# HealthMonitor.net
KiCad netlist of a schematic drawn in EAGLE
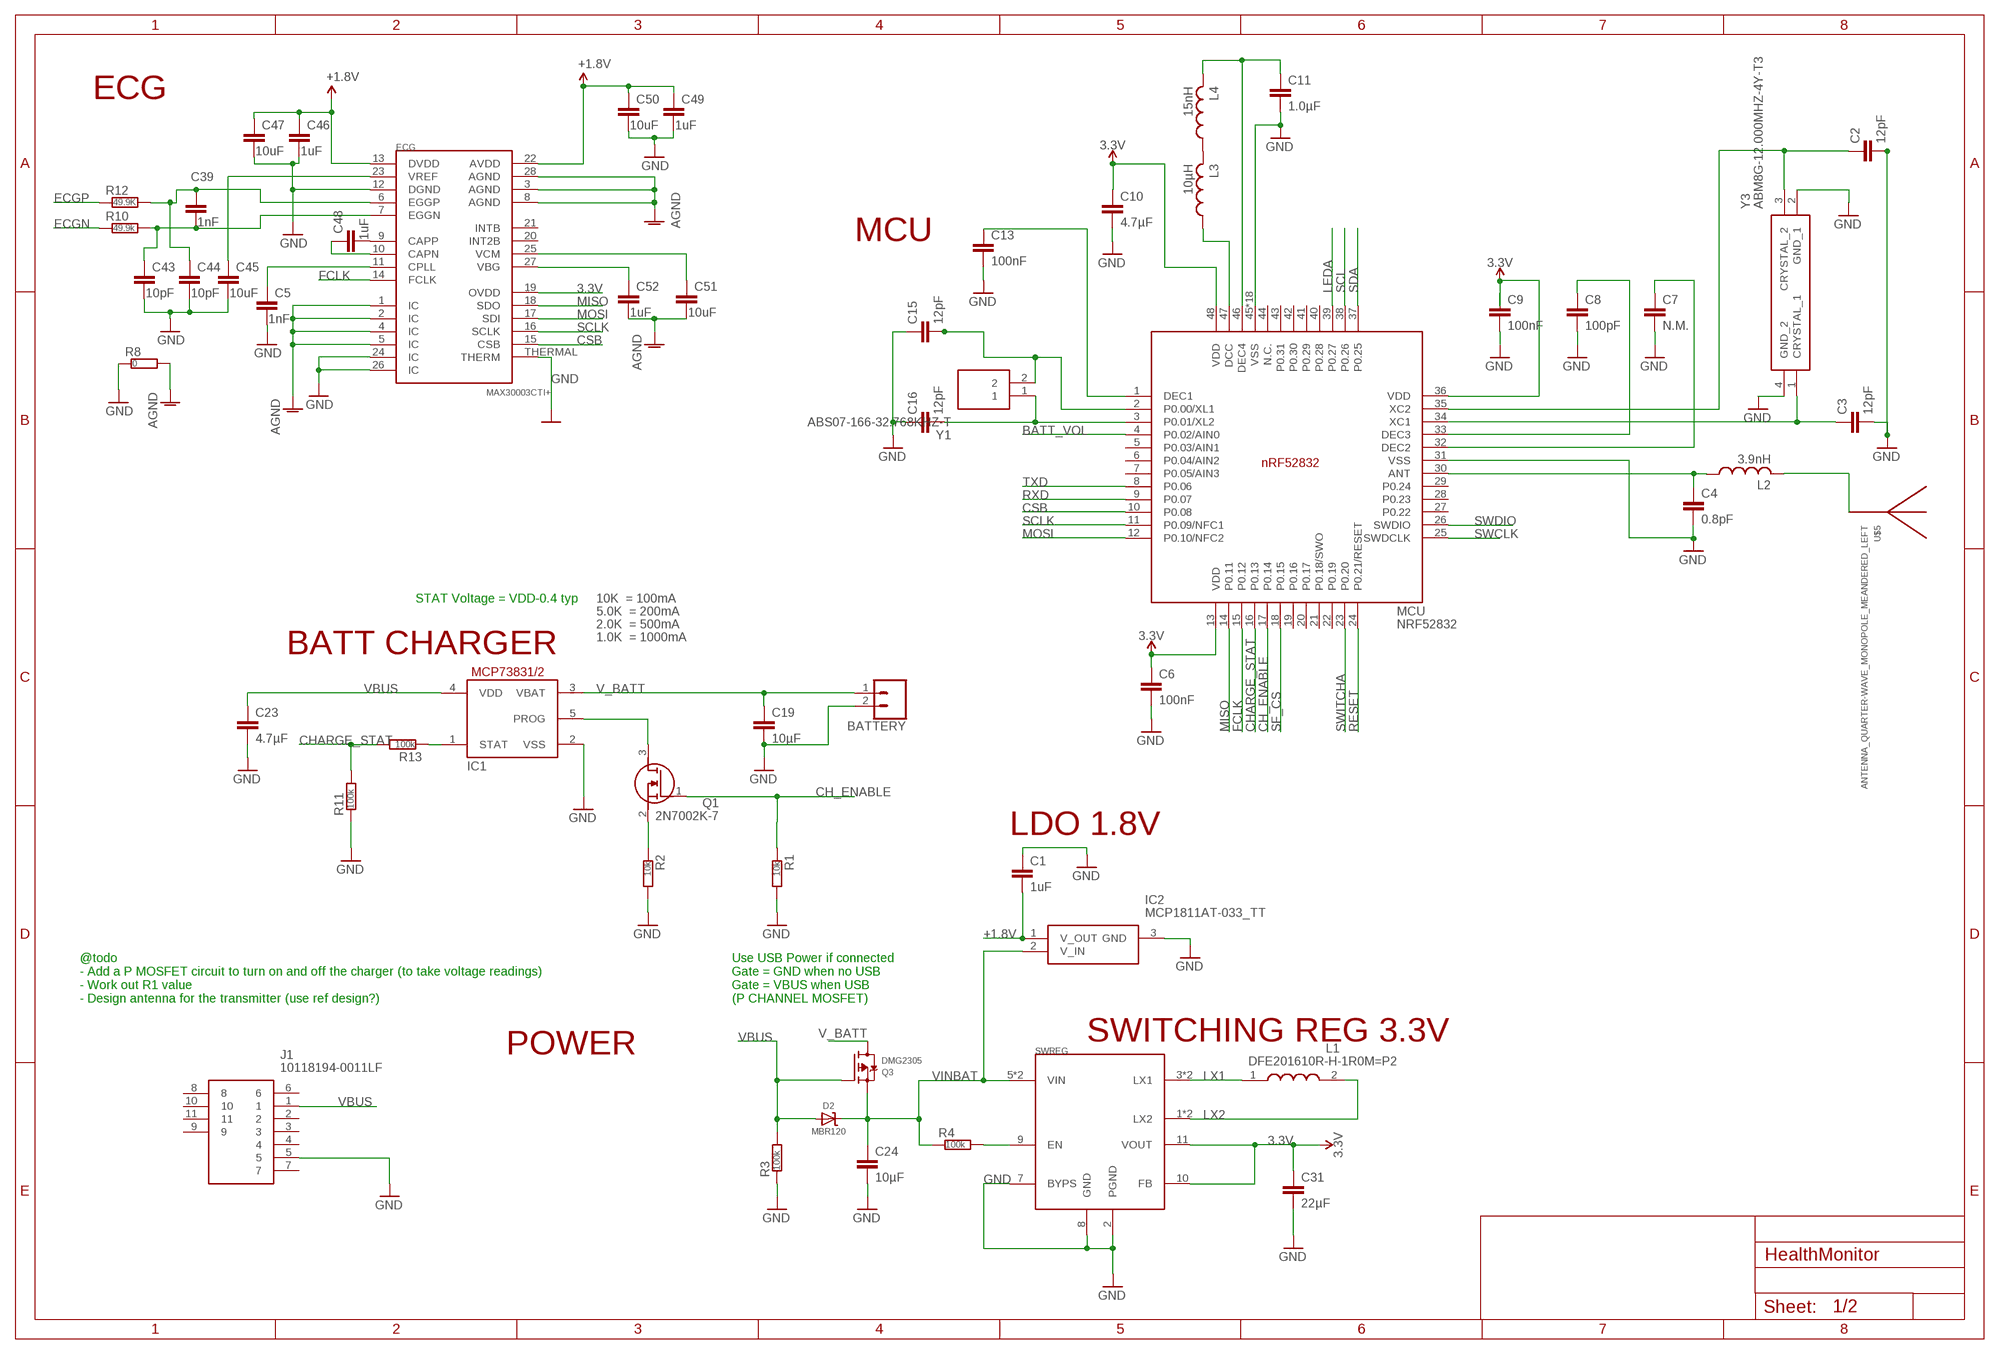
[diagram p0: schematic, sheet 1]
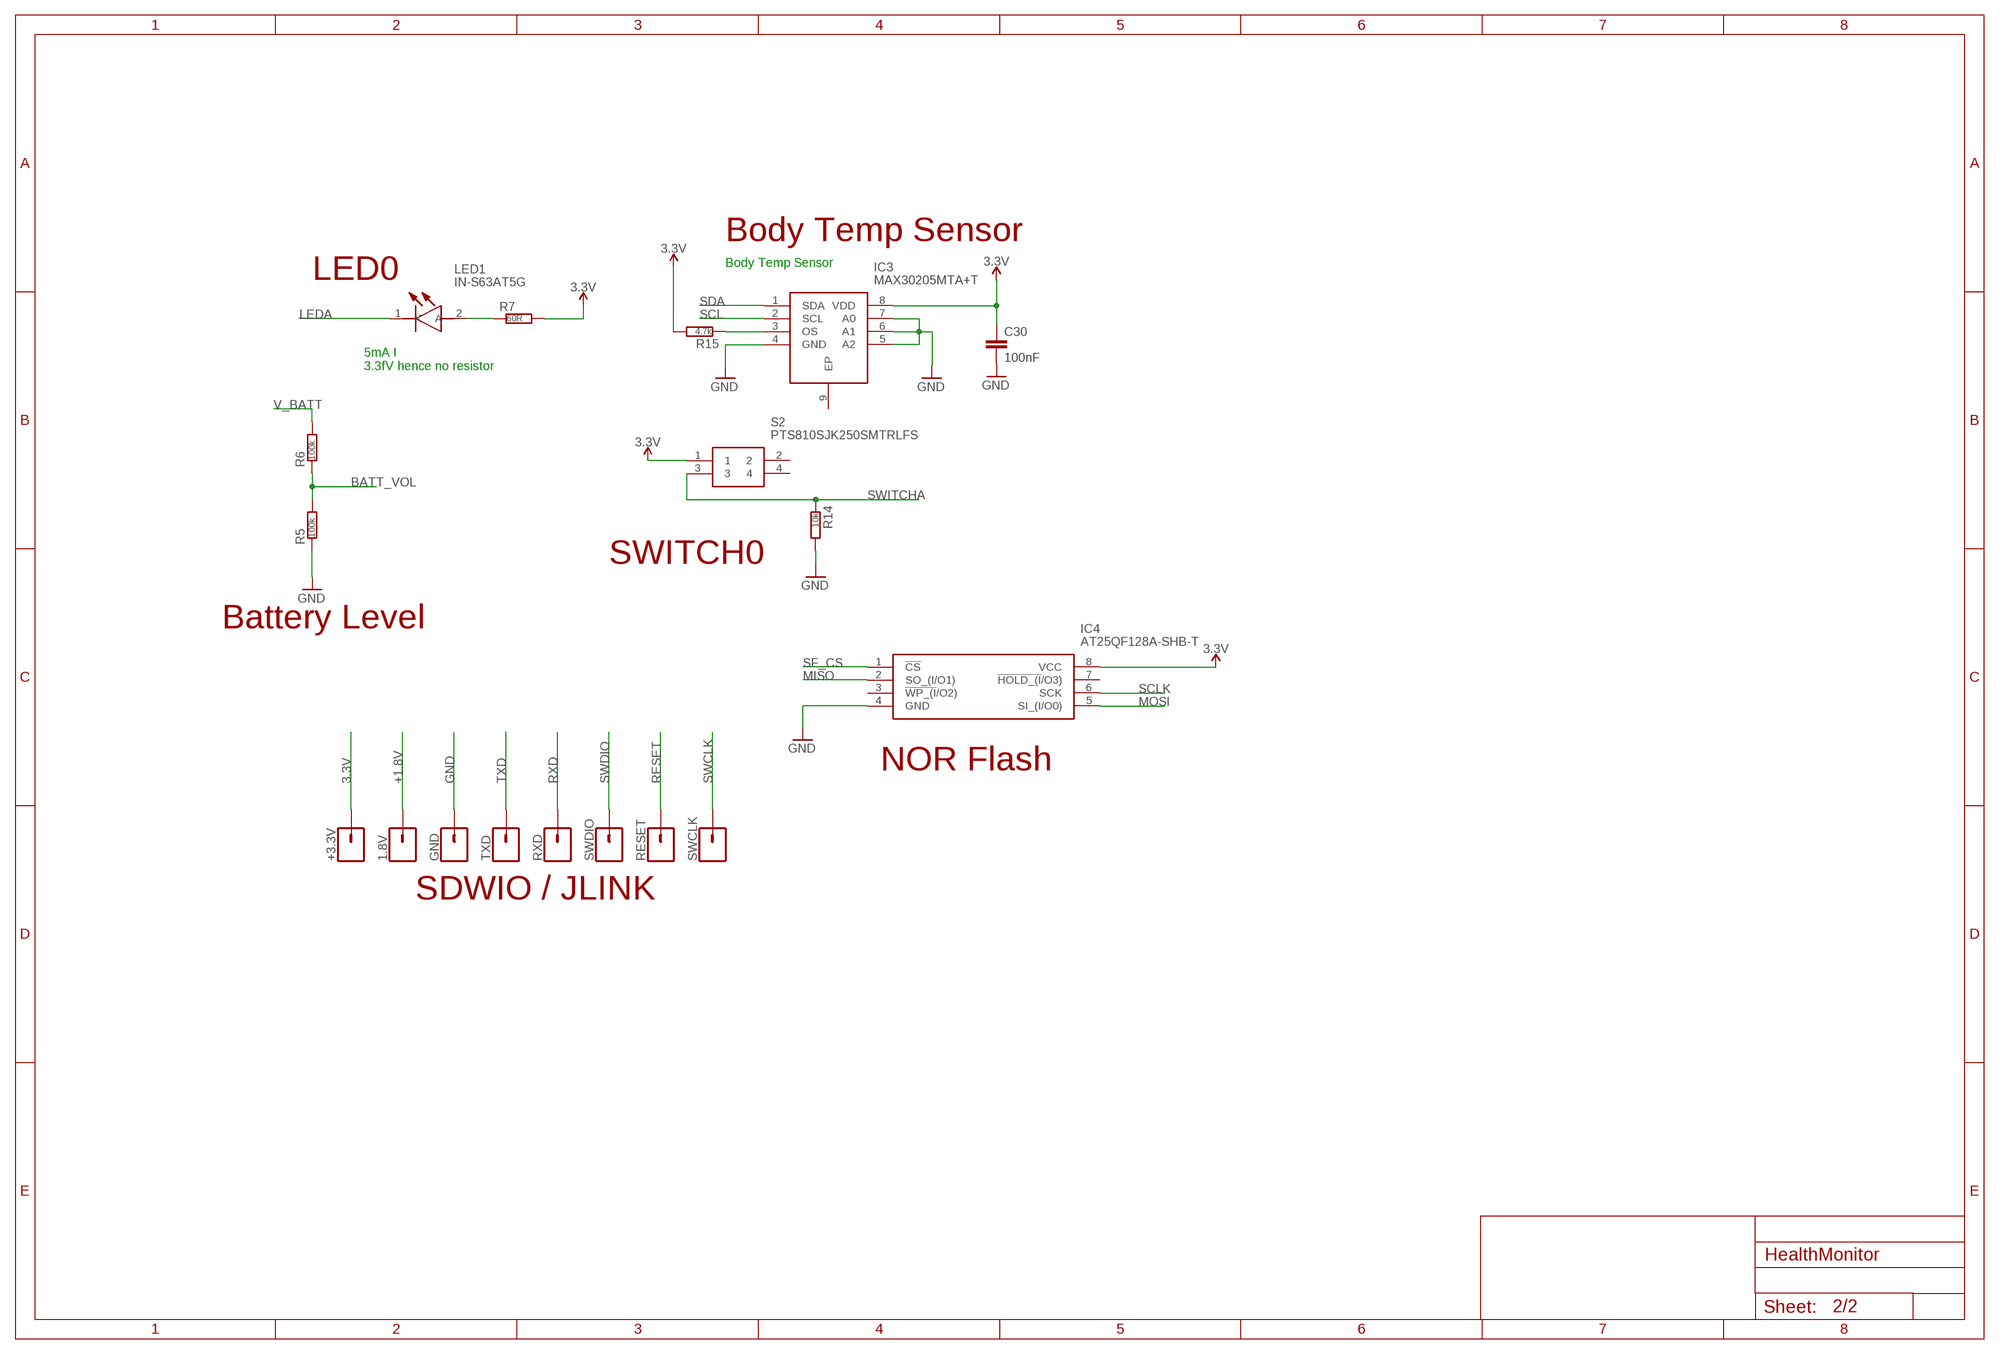
[diagram p1: schematic, sheet 2]

(export (version "E")
  (design (tool "Eeschema 10.0.6"))
  (components
    (comp (ref "BATTERY")
      (value "CONN_02")
      (footprint "eagle-import:1X02")
      (libsource (lib "eagle-import") (part "CONN_02"))
    )
    (comp (ref "C1")
      (value "1uF")
      (footprint "eagle-import:RESC0603_N")
      (libsource (lib "eagle-import") (part "CAPACITOR_0603_N"))
    )
    (comp (ref "C2")
      (value "12pF")
      (footprint "eagle-import:RESC0603_N")
      (libsource (lib "eagle-import") (part "CAPACITOR_0603_N"))
    )
    (comp (ref "C3")
      (value "12pF")
      (footprint "eagle-import:RESC0603_N")
      (libsource (lib "eagle-import") (part "CAPACITOR_0603_N"))
    )
    (comp (ref "C4")
      (value "0.8pF")
      (footprint "eagle-import:RESC0603_N")
      (libsource (lib "eagle-import") (part "CAPACITOR_0603_N"))
    )
    (comp (ref "C5")
      (value "1nF")
      (footprint "eagle-import:RESC0603_N")
      (libsource (lib "eagle-import") (part "CAPACITOR_0603_N"))
    )
    (comp (ref "C6")
      (value "100nF")
      (footprint "eagle-import:RESC0603_N")
      (libsource (lib "eagle-import") (part "CAPACITOR_0603_N"))
    )
    (comp (ref "C7")
      (value "N.M.")
      (footprint "eagle-import:RESC0603_N")
      (libsource (lib "eagle-import") (part "CAPACITOR_0603_N"))
    )
    (comp (ref "C8")
      (value "100pF")
      (footprint "eagle-import:RESC0603_N")
      (libsource (lib "eagle-import") (part "CAPACITOR_0603_N"))
    )
    (comp (ref "C9")
      (value "100nF")
      (footprint "eagle-import:RESC0603_N")
      (libsource (lib "eagle-import") (part "CAPACITOR_0603_N"))
    )
    (comp (ref "C10")
      (value "4.7µF")
      (footprint "eagle-import:RESC0603_N")
      (libsource (lib "eagle-import") (part "CAPACITOR_0603_N"))
    )
    (comp (ref "C11")
      (value "1.0µF")
      (footprint "eagle-import:RESC0603_N")
      (libsource (lib "eagle-import") (part "CAPACITOR_0603_N"))
    )
    (comp (ref "C13")
      (value "100nF")
      (footprint "eagle-import:RESC0603_N")
      (libsource (lib "eagle-import") (part "CAPACITOR_0603_N"))
    )
    (comp (ref "C15")
      (value "12pF")
      (footprint "eagle-import:RESC0603_N")
      (libsource (lib "eagle-import") (part "CAPACITOR_0603_N"))
    )
    (comp (ref "C16")
      (value "12pF")
      (footprint "eagle-import:RESC0603_N")
      (libsource (lib "eagle-import") (part "CAPACITOR_0603_N"))
    )
    (comp (ref "C19")
      (value "10µF")
      (footprint "eagle-import:RESC0603_N")
      (libsource (lib "eagle-import") (part "CAPACITOR_0603_N"))
    )
    (comp (ref "C23")
      (value "4.7µF")
      (footprint "eagle-import:RESC0603_N")
      (libsource (lib "eagle-import") (part "CAPACITOR_0603_N"))
    )
    (comp (ref "C24")
      (value "10µF")
      (footprint "eagle-import:RESC0603_N")
      (libsource (lib "eagle-import") (part "CAPACITOR_0603_N"))
    )
    (comp (ref "C31")
      (value "22µF")
      (footprint "eagle-import:RESC0603_N")
      (libsource (lib "eagle-import") (part "CAPACITOR_0603_N"))
    )
    (comp (ref "C39")
      (value "1nF")
      (footprint "eagle-import:RESC0603_N")
      (libsource (lib "eagle-import") (part "CAPACITOR_0603_N"))
    )
    (comp (ref "C43")
      (value "10pF")
      (footprint "eagle-import:RESC0603_N")
      (libsource (lib "eagle-import") (part "CAPACITOR_0603_N"))
    )
    (comp (ref "C44")
      (value "10pF")
      (footprint "eagle-import:RESC0603_N")
      (libsource (lib "eagle-import") (part "CAPACITOR_0603_N"))
    )
    (comp (ref "C45")
      (value "10uF")
      (footprint "eagle-import:RESC0603_N")
      (libsource (lib "eagle-import") (part "CAPACITOR_0603_N"))
    )
    (comp (ref "C46")
      (value "1uF")
      (footprint "eagle-import:RESC0603_N")
      (libsource (lib "eagle-import") (part "CAPACITOR_0603_N"))
    )
    (comp (ref "C47")
      (value "10uF")
      (footprint "eagle-import:RESC0603_N")
      (libsource (lib "eagle-import") (part "CAPACITOR_0603_N"))
    )
    (comp (ref "C48")
      (value "1uF")
      (footprint "eagle-import:RESC0603_N")
      (libsource (lib "eagle-import") (part "CAPACITOR_0603_N"))
    )
    (comp (ref "C49")
      (value "1uF")
      (footprint "eagle-import:RESC0603_N")
      (libsource (lib "eagle-import") (part "CAPACITOR_0603_N"))
    )
    (comp (ref "C50")
      (value "10uF")
      (footprint "eagle-import:RESC0603_N")
      (libsource (lib "eagle-import") (part "CAPACITOR_0603_N"))
    )
    (comp (ref "C51")
      (value "10uF")
      (footprint "eagle-import:RESC0603_N")
      (libsource (lib "eagle-import") (part "CAPACITOR_0603_N"))
    )
    (comp (ref "C52")
      (value "1uF")
      (footprint "eagle-import:RESC0603_N")
      (libsource (lib "eagle-import") (part "CAPACITOR_0603_N"))
    )
    (comp (ref "D2")
      (value "MBR120")
      (footprint "eagle-import:SOD-123")
      (libsource (lib "eagle-import") (part "DIODE-SCHOTTKYSOD-123"))
    )
    (comp (ref "ECG")
      (value "MAX30003CTI+")
      (footprint "eagle-import:QFN-28")
      (libsource (lib "eagle-import") (part "MAX30003"))
    )
    (comp (ref "IC1")
      (value "MCP73831/OT")
      (footprint "eagle-import:SOT23-5L")
      (libsource (lib "eagle-import") (part "MCP73831/OT"))
    )
    (comp (ref "IC2")
      (value "MCP1811AT-033_TT")
      (footprint "eagle-import:SOT95P237X112-3N")
      (fields
        (field (name "MANUFACTURER_PART_NUMBER") "MCP1811AT-033/TT")
        (field (name "MOUSER_PART_NUMBER") "579-MCP1811AT-033/TT")
      )
      (libsource (lib "eagle-import") (part "MCP1811AT-033_TT"))
    )
    (comp (ref "J1")
      (value "10118194-0011LF")
      (footprint "eagle-import:101181940011LF")
      (fields (field (name "MOUSER_PART_NUMBER") "649-10118194-0011LF"))
      (libsource (lib "eagle-import") (part "10118194-0011LF"))
    )
    (comp (ref "L1")
      (value "DFE201610R-H-1R0M=P2")
      (footprint "eagle-import:INDC2016X100N")
      (fields (field (name "MOUSER_PART_NUMBER") "81-DFE201610RH1R0MP2"))
      (libsource (lib "eagle-import") (part "DFE201610R-H-1R0M=P2"))
    )
    (comp (ref "L2")
      (value "3.9nH")
      (footprint "eagle-import:RESC0603_N")
      (libsource (lib "eagle-import") (part "INDUCTOR_0603_N"))
    )
    (comp (ref "L3")
      (value "10µH")
      (footprint "eagle-import:RESC0603_N")
      (libsource (lib "eagle-import") (part "INDUCTOR_0603_N"))
    )
    (comp (ref "L4")
      (value "15nH")
      (footprint "eagle-import:RESC0603_N")
      (libsource (lib "eagle-import") (part "INDUCTOR_0603_N"))
    )
    (comp (ref "MCU")
      (value "NRF52832")
      (footprint "eagle-import:QFN40P600X600X90-48_N")
      (libsource (lib "eagle-import") (part "NRF52832"))
    )
    (comp (ref "Q1")
      (value "2N7002K-7")
      (footprint "eagle-import:SOT96P240X100-3N")
      (fields (field (name "MOUSER_PART_NUMBER") "621-2N7002K-7") (field (name "RS_PART_NUMBER") "7703383"))
      (libsource (lib "eagle-import") (part "2N7002K-7"))
    )
    (comp (ref "Q3")
      (value "DMG2305")
      (footprint "eagle-import:SOT23-R")
      (libsource (lib "eagle-import") (part "MOSFET-P"))
    )
    (comp (ref "R1")
      (value "10k")
      (footprint "eagle-import:RESC0603_N")
      (libsource (lib "eagle-import") (part "RESISTOR_0603_N"))
    )
    (comp (ref "R2")
      (value "10k")
      (footprint "eagle-import:RESC0603_N")
      (libsource (lib "eagle-import") (part "RESISTOR_0603_N"))
    )
    (comp (ref "R3")
      (value "100k")
      (footprint "eagle-import:RESC0603_N")
      (libsource (lib "eagle-import") (part "RESISTOR_0603_N"))
    )
    (comp (ref "R4")
      (value "100k")
      (footprint "eagle-import:RESC0603_N")
      (libsource (lib "eagle-import") (part "RESISTOR_0603_N"))
    )
    (comp (ref "R8")
      (value "0")
      (footprint "eagle-import:RESC0603_N")
      (libsource (lib "eagle-import") (part "RESISTOR_0603_N"))
    )
    (comp (ref "R10")
      (value "49.9k")
      (footprint "eagle-import:RESC0603_N")
      (libsource (lib "eagle-import") (part "RESISTOR_0603_N"))
    )
    (comp (ref "R11")
      (value "100k")
      (footprint "eagle-import:RESC0603_N")
      (libsource (lib "eagle-import") (part "RESISTOR_0603_N"))
    )
    (comp (ref "R12")
      (value "49.9K")
      (footprint "eagle-import:RESC0603_N")
      (libsource (lib "eagle-import") (part "RESISTOR_0603_N"))
    )
    (comp (ref "R13")
      (value "100k")
      (footprint "eagle-import:RESC0603_N")
      (libsource (lib "eagle-import") (part "RESISTOR_0603_N"))
    )
    (comp (ref "SWREG")
      (value "SL9120IRVR")
      (footprint "eagle-import:TQFN-12")
      (libsource (lib "eagle-import") (part "SL9120IRVR"))
    )
    (comp (ref "U$5")
      (value "ANTENNA_QUARTER-WAVE_MONOPOLE_MEANDERED_LEFT")
      (footprint "eagle-import:QWMP_MEANDERED_LEFT_+6")
      (libsource (lib "eagle-import") (part "ANTENNA_QUARTER-WAVE_MONOPOLE_MEANDERED_LEFT"))
    )
    (comp (ref "Y1")
      (value "ABS07-166-32.768KHZ-T")
      (footprint "eagle-import:ABS0716632768KHZT")
      (fields
        (field (name "MOUSER_PART_NUMBER") "815-ABS0716632.768KT")
        (field (name "RS_PART_NUMBER") "1753474P")
      )
      (libsource (lib "eagle-import") (part "ABS07-166-32.768KHZ-T"))
    )
    (comp (ref "Y3")
      (value "ABM8G-12.000MHZ-4Y-T3")
      (footprint "eagle-import:ABM8G16000MHZB4YT")
      (fields
        (field (name "MOUSER_PART_NUMBER") "815-ABM8G-12-4YT3")
        (field (name "RS_PART_NUMBER") "1712832P")
      )
      (libsource (lib "eagle-import") (part "ABM8G-12.000MHZ-4Y-T3"))
    )
    (comp (ref "+3.3V")
      (value "CONN_01")
      (footprint "eagle-import:1X01")
      (libsource (lib "eagle-import") (part "CONN_01"))
    )
    (comp (ref "1.8V")
      (value "CONN_01")
      (footprint "eagle-import:1X01")
      (libsource (lib "eagle-import") (part "CONN_01"))
    )
    (comp (ref "C30")
      (value "100nF")
      (footprint "eagle-import:RESC0603_N")
      (libsource (lib "eagle-import") (part "CAPACITOR_0603_N"))
    )
    (comp (ref "GND")
      (value "CONN_01")
      (footprint "eagle-import:1X01")
      (libsource (lib "eagle-import") (part "CONN_01"))
    )
    (comp (ref "IC3")
      (value "MAX30205MTA+T")
      (footprint "eagle-import:SON65P300X300X80-9N")
      (fields (field (name "MOUSER_PART_NUMBER") "700-MAX30205MTA+T"))
      (libsource (lib "eagle-import") (part "MAX30205MTA+T"))
    )
    (comp (ref "IC4")
      (value "AT25QF128A-SHB-T")
      (footprint "eagle-import:SOIC127P790X216-8N")
      (fields (field (name "MOUSER_PART_NUMBER") "988-AT25QF128A-SHB-T"))
      (libsource (lib "eagle-import") (part "AT25QF128A-SHB-T"))
    )
    (comp (ref "LED1")
      (value "IN-S63AT5G")
      (footprint "eagle-import:LEDM168X39N")
      (fields (field (name "MOUSER_PART_NUMBER") "743-IN-S63AT5G"))
      (libsource (lib "eagle-import") (part "IN-S63AT5G"))
    )
    (comp (ref "R5")
      (value "100k")
      (footprint "eagle-import:RESC0603_N")
      (libsource (lib "eagle-import") (part "RESISTOR_0603_N"))
    )
    (comp (ref "R6")
      (value "100k")
      (footprint "eagle-import:RESC0603_N")
      (libsource (lib "eagle-import") (part "RESISTOR_0603_N"))
    )
    (comp (ref "R7")
      (value "60R")
      (footprint "eagle-import:RESC0603_N")
      (libsource (lib "eagle-import") (part "RESISTOR_0603_N"))
    )
    (comp (ref "R14")
      (value "10k")
      (footprint "eagle-import:RESC0603_N")
      (libsource (lib "eagle-import") (part "RESISTOR_0603_N"))
    )
    (comp (ref "R15")
      (value "4.7k")
      (footprint "eagle-import:RESC0603_N")
      (libsource (lib "eagle-import") (part "RESISTOR_0603_N"))
    )
    (comp (ref "RESET")
      (value "CONN_01")
      (footprint "eagle-import:1X01")
      (libsource (lib "eagle-import") (part "CONN_01"))
    )
    (comp (ref "RXD")
      (value "CONN_01")
      (footprint "eagle-import:1X01")
      (libsource (lib "eagle-import") (part "CONN_01"))
    )
    (comp (ref "S2")
      (value "PTS810SJK250SMTRLFS")
      (footprint "eagle-import:PTS810SJG250SMTRLFS")
      (fields
        (field (name "MOUSER_PART_NUMBER") "611-PTS810SJK250SMTR")
        (field (name "RS_PART_NUMBER") "1359396P")
      )
      (libsource (lib "eagle-import") (part "PTS810SJK250SMTRLFS"))
    )
    (comp (ref "SWCLK")
      (value "CONN_01")
      (footprint "eagle-import:1X01")
      (libsource (lib "eagle-import") (part "CONN_01"))
    )
    (comp (ref "SWDIO")
      (value "CONN_01")
      (footprint "eagle-import:1X01")
      (libsource (lib "eagle-import") (part "CONN_01"))
    )
    (comp (ref "TXD")
      (value "CONN_01")
      (footprint "eagle-import:1X01")
      (libsource (lib "eagle-import") (part "CONN_01"))
    )
  )
  (nets
    (net (code "1") (name "+1.8V") (class "Default")
      (node (ref "1.8V") (pin "1") (pinfunction "1_1") (pintype "passive"))
      (node (ref "C1") (pin "2") (pinfunction "2_2") (pintype "passive"))
      (node (ref "C46") (pin "1") (pinfunction "1_1") (pintype "passive"))
      (node (ref "C47") (pin "1") (pinfunction "1_1") (pintype "passive"))
      (node (ref "C49") (pin "1") (pinfunction "1_1") (pintype "passive"))
      (node (ref "C50") (pin "1") (pinfunction "1_1") (pintype "passive"))
      (node (ref "ECG") (pin "13") (pinfunction "DVDD_13") (pintype "bidirectional"))
      (node (ref "ECG") (pin "22") (pinfunction "AVDD_22") (pintype "bidirectional"))
      (node (ref "IC2") (pin "1") (pinfunction "V_OUT_1") (pintype "bidirectional"))
    )
    (net (code "2") (name "3.3V") (class "Default")
      (node (ref "+3.3V") (pin "1") (pinfunction "1_1") (pintype "passive"))
      (node (ref "C10") (pin "1") (pinfunction "1_1") (pintype "passive"))
      (node (ref "C30") (pin "1") (pinfunction "1_1") (pintype "passive"))
      (node (ref "C31") (pin "1") (pinfunction "1_1") (pintype "passive"))
      (node (ref "C6") (pin "1") (pinfunction "1_1") (pintype "passive"))
      (node (ref "C9") (pin "1") (pinfunction "1_1") (pintype "passive"))
      (node (ref "ECG") (pin "19") (pinfunction "OVDD_19") (pintype "bidirectional"))
      (node (ref "IC3") (pin "8") (pinfunction "VDD_8") (pintype "bidirectional"))
      (node (ref "IC4") (pin "8") (pinfunction "VCC_8") (pintype "bidirectional"))
      (node (ref "MCU") (pin "13") (pinfunction "VDD_13") (pintype "power_in"))
      (node (ref "MCU") (pin "36") (pinfunction "VDD_36") (pintype "power_in"))
      (node (ref "MCU") (pin "48") (pinfunction "VDD_48") (pintype "power_in"))
      (node (ref "R15") (pin "2") (pinfunction "2_2") (pintype "passive"))
      (node (ref "R7") (pin "2") (pinfunction "2_2") (pintype "passive"))
      (node (ref "S2") (pin "1") (pinfunction "1_1") (pintype "bidirectional"))
      (node (ref "SWREG") (pin "10") (pinfunction "FB_10") (pintype "bidirectional"))
      (node (ref "SWREG") (pin "11") (pinfunction "VOUT_11") (pintype "bidirectional"))
    )
    (net (code "3") (name "AGND") (class "Default")
      (node (ref "C51") (pin "2") (pinfunction "2_2") (pintype "passive"))
      (node (ref "C52") (pin "2") (pinfunction "2_2") (pintype "passive"))
      (node (ref "ECG") (pin "1") (pinfunction "IC_1") (pintype "bidirectional"))
      (node (ref "ECG") (pin "2") (pinfunction "IC_2") (pintype "bidirectional"))
      (node (ref "ECG") (pin "28") (pinfunction "AGND_28") (pintype "bidirectional"))
      (node (ref "ECG") (pin "3") (pinfunction "AGND_3") (pintype "bidirectional"))
      (node (ref "ECG") (pin "4") (pinfunction "IC_4") (pintype "bidirectional"))
      (node (ref "ECG") (pin "5") (pinfunction "IC_5") (pintype "bidirectional"))
      (node (ref "ECG") (pin "8") (pinfunction "AGND_8") (pintype "bidirectional"))
      (node (ref "R8") (pin "2") (pinfunction "2_2") (pintype "passive"))
    )
    (net (code "4") (name "BATT_VOL") (class "Default")
      (node (ref "MCU") (pin "4") (pinfunction "P0.02/AIN0_4") (pintype "bidirectional"))
      (node (ref "R5") (pin "2") (pinfunction "2_2") (pintype "passive"))
      (node (ref "R6") (pin "1") (pinfunction "1_1") (pintype "passive"))
    )
    (net (code "5") (name "CHARGE_STAT") (class "Default")
      (node (ref "MCU") (pin "16") (pinfunction "P0.13_16") (pintype "bidirectional"))
      (node (ref "R11") (pin "2") (pinfunction "2_2") (pintype "passive"))
      (node (ref "R13") (pin "2") (pinfunction "2_2") (pintype "passive"))
    )
    (net (code "6") (name "CH_ENABLE") (class "Default")
      (node (ref "MCU") (pin "17") (pinfunction "P0.14_17") (pintype "bidirectional"))
      (node (ref "Q1") (pin "1") (pinfunction "G_1") (pintype "bidirectional"))
      (node (ref "R1") (pin "1") (pinfunction "1_1") (pintype "passive"))
    )
    (net (code "7") (name "CSB") (class "Default")
      (node (ref "ECG") (pin "15") (pinfunction "CSB_15") (pintype "bidirectional"))
      (node (ref "MCU") (pin "10") (pinfunction "P0.08_10") (pintype "bidirectional"))
    )
    (net (code "8") (name "ECGN") (class "Default")
      (node (ref "R10") (pin "1") (pinfunction "1_1") (pintype "passive"))
    )
    (net (code "9") (name "ECGP") (class "Default")
      (node (ref "R12") (pin "1") (pinfunction "1_1") (pintype "passive"))
    )
    (net (code "10") (name "FCLK") (class "Default")
      (node (ref "ECG") (pin "14") (pinfunction "FCLK_14") (pintype "bidirectional"))
      (node (ref "MCU") (pin "15") (pinfunction "P0.12_15") (pintype "bidirectional"))
    )
    (net (code "11") (name "GND") (class "Default")
      (node (ref "BATTERY") (pin "2") (pinfunction "2_2") (pintype "passive"))
      (node (ref "C1") (pin "1") (pinfunction "1_1") (pintype "passive"))
      (node (ref "C10") (pin "2") (pinfunction "2_2") (pintype "passive"))
      (node (ref "C11") (pin "2") (pinfunction "2_2") (pintype "passive"))
      (node (ref "C13") (pin "2") (pinfunction "2_2") (pintype "passive"))
      (node (ref "C15") (pin "1") (pinfunction "1_1") (pintype "passive"))
      (node (ref "C16") (pin "1") (pinfunction "1_1") (pintype "passive"))
      (node (ref "C19") (pin "2") (pinfunction "2_2") (pintype "passive"))
      (node (ref "C2") (pin "2") (pinfunction "2_2") (pintype "passive"))
      (node (ref "C23") (pin "2") (pinfunction "2_2") (pintype "passive"))
      (node (ref "C24") (pin "2") (pinfunction "2_2") (pintype "passive"))
      (node (ref "C3") (pin "2") (pinfunction "2_2") (pintype "passive"))
      (node (ref "C30") (pin "2") (pinfunction "2_2") (pintype "passive"))
      (node (ref "C31") (pin "2") (pinfunction "2_2") (pintype "passive"))
      (node (ref "C4") (pin "2") (pinfunction "2_2") (pintype "passive"))
      (node (ref "C43") (pin "2") (pinfunction "2_2") (pintype "passive"))
      (node (ref "C44") (pin "2") (pinfunction "2_2") (pintype "passive"))
      (node (ref "C45") (pin "2") (pinfunction "2_2") (pintype "passive"))
      (node (ref "C46") (pin "2") (pinfunction "2_2") (pintype "passive"))
      (node (ref "C47") (pin "2") (pinfunction "2_2") (pintype "passive"))
      (node (ref "C49") (pin "2") (pinfunction "2_2") (pintype "passive"))
      (node (ref "C5") (pin "2") (pinfunction "2_2") (pintype "passive"))
      (node (ref "C50") (pin "2") (pinfunction "2_2") (pintype "passive"))
      (node (ref "C6") (pin "2") (pinfunction "2_2") (pintype "passive"))
      (node (ref "C7") (pin "2") (pinfunction "2_2") (pintype "passive"))
      (node (ref "C8") (pin "2") (pinfunction "2_2") (pintype "passive"))
      (node (ref "C9") (pin "2") (pinfunction "2_2") (pintype "passive"))
      (node (ref "ECG") (pin "12") (pinfunction "DGND_12") (pintype "bidirectional"))
      (node (ref "ECG") (pin "24") (pinfunction "IC_24") (pintype "bidirectional"))
      (node (ref "ECG") (pin "26") (pinfunction "IC_26") (pintype "bidirectional"))
      (node (ref "ECG") (pin "THERMAL") (pinfunction "THERM_THERMAL") (pintype "bidirectional"))
      (node (ref "GND") (pin "1") (pinfunction "1_1") (pintype "passive"))
      (node (ref "IC1") (pin "2") (pinfunction "VSS_2") (pintype "power_in"))
      (node (ref "IC2") (pin "3") (pinfunction "GND_3") (pintype "bidirectional"))
      (node (ref "IC3") (pin "4") (pinfunction "GND_4") (pintype "bidirectional"))
      (node (ref "IC3") (pin "5") (pinfunction "A2_5") (pintype "bidirectional"))
      (node (ref "IC3") (pin "6") (pinfunction "A1_6") (pintype "bidirectional"))
      (node (ref "IC3") (pin "7") (pinfunction "A0_7") (pintype "bidirectional"))
      (node (ref "IC4") (pin "4") (pinfunction "GND_4") (pintype "bidirectional"))
      (node (ref "J1") (pin "5") (pinfunction "5_5") (pintype "bidirectional"))
      (node (ref "MCU") (pin "31") (pinfunction "VSS_31") (pintype "bidirectional"))
      (node (ref "MCU") (pin "45") (pinfunction "VSS_45") (pintype "power_in"))
      (node (ref "MCU") (pin "PAD") (pinfunction "VSS_PAD") (pintype "power_in"))
      (node (ref "MCU") (pin "PAD@VIA01") (pinfunction "VSS_PAD@VIA01") (pintype "power_in"))
      (node (ref "MCU") (pin "PAD@VIA02") (pinfunction "VSS_PAD@VIA02") (pintype "power_in"))
      (node (ref "MCU") (pin "PAD@VIA03") (pinfunction "VSS_PAD@VIA03") (pintype "power_in"))
      (node (ref "MCU") (pin "PAD@VIA04") (pinfunction "VSS_PAD@VIA04") (pintype "power_in"))
      (node (ref "MCU") (pin "PAD@VIA05") (pinfunction "VSS_PAD@VIA05") (pintype "power_in"))
      (node (ref "MCU") (pin "PAD@VIA06") (pinfunction "VSS_PAD@VIA06") (pintype "power_in"))
      (node (ref "MCU") (pin "PAD@VIA07") (pinfunction "VSS_PAD@VIA07") (pintype "power_in"))
      (node (ref "MCU") (pin "PAD@VIA08") (pinfunction "VSS_PAD@VIA08") (pintype "power_in"))
      (node (ref "MCU") (pin "PAD@VIA09") (pinfunction "VSS_PAD@VIA09") (pintype "power_in"))
      (node (ref "MCU") (pin "PAD@VIA10") (pinfunction "VSS_PAD@VIA10") (pintype "power_in"))
      (node (ref "MCU") (pin "PAD@VIA11") (pinfunction "VSS_PAD@VIA11") (pintype "power_in"))
      (node (ref "MCU") (pin "PAD@VIA12") (pinfunction "VSS_PAD@VIA12") (pintype "power_in"))
      (node (ref "MCU") (pin "PAD@VIA13") (pinfunction "VSS_PAD@VIA13") (pintype "power_in"))
      (node (ref "MCU") (pin "PAD@VIA14") (pinfunction "VSS_PAD@VIA14") (pintype "power_in"))
      (node (ref "MCU") (pin "PAD@VIA15") (pinfunction "VSS_PAD@VIA15") (pintype "power_in"))
      (node (ref "MCU") (pin "PAD@VIA16") (pinfunction "VSS_PAD@VIA16") (pintype "power_in"))
      (node (ref "R1") (pin "2") (pinfunction "2_2") (pintype "passive"))
      (node (ref "R11") (pin "1") (pinfunction "1_1") (pintype "passive"))
      (node (ref "R14") (pin "2") (pinfunction "2_2") (pintype "passive"))
      (node (ref "R2") (pin "2") (pinfunction "2_2") (pintype "passive"))
      (node (ref "R3") (pin "1") (pinfunction "1_1") (pintype "passive"))
      (node (ref "R5") (pin "1") (pinfunction "1_1") (pintype "passive"))
      (node (ref "R8") (pin "1") (pinfunction "1_1") (pintype "passive"))
      (node (ref "SWREG") (pin "2") (pinfunction "PGND_2") (pintype "bidirectional"))
      (node (ref "SWREG") (pin "7") (pinfunction "BYPS_7") (pintype "bidirectional"))
      (node (ref "SWREG") (pin "8") (pinfunction "GND_8") (pintype "bidirectional"))
      (node (ref "Y3") (pin "2") (pinfunction "GND_1_2") (pintype "bidirectional"))
      (node (ref "Y3") (pin "4") (pinfunction "GND_2_4") (pintype "bidirectional"))
    )
    (net (code "12") (name "LEDA") (class "Default")
      (node (ref "LED1") (pin "1") (pinfunction "K_1") (pintype "bidirectional"))
      (node (ref "MCU") (pin "39") (pinfunction "P0.27_39") (pintype "bidirectional"))
    )
    (net (code "13") (name "LX1") (class "Default")
      (node (ref "L1") (pin "1") (pinfunction "1_1") (pintype "bidirectional"))
      (node (ref "SWREG") (pin "3") (pinfunction "LX1_3") (pintype "bidirectional"))
      (node (ref "SWREG") (pin "4") (pinfunction "LX1_4") (pintype "bidirectional"))
    )
    (net (code "14") (name "LX2") (class "Default")
      (node (ref "L1") (pin "2") (pinfunction "2_2") (pintype "bidirectional"))
      (node (ref "SWREG") (pin "1") (pinfunction "LX2_1") (pintype "bidirectional"))
      (node (ref "SWREG") (pin "12") (pinfunction "LX2_12") (pintype "bidirectional"))
    )
    (net (code "15") (name "MISO") (class "Default")
      (node (ref "ECG") (pin "18") (pinfunction "SDO_18") (pintype "bidirectional"))
      (node (ref "IC4") (pin "2") (pinfunction "SO_(I/O1)_2") (pintype "bidirectional"))
      (node (ref "MCU") (pin "14") (pinfunction "P0.11_14") (pintype "bidirectional"))
    )
    (net (code "16") (name "MOSI") (class "Default")
      (node (ref "ECG") (pin "17") (pinfunction "SDI_17") (pintype "bidirectional"))
      (node (ref "IC4") (pin "5") (pinfunction "SI_(I/O0)_5") (pintype "bidirectional"))
      (node (ref "MCU") (pin "12") (pinfunction "P0.10/NFC2_12") (pintype "bidirectional"))
    )
    (net (code "17") (name "Net-(ECG-CAPN)") (class "Default")
      (node (ref "C48") (pin "1") (pinfunction "1_1") (pintype "passive"))
      (node (ref "ECG") (pin "10") (pinfunction "CAPN_10") (pintype "bidirectional"))
    )
    (net (code "18") (name "Net-(ECG-CAPP)") (class "Default")
      (node (ref "C48") (pin "2") (pinfunction "2_2") (pintype "passive"))
      (node (ref "ECG") (pin "9") (pinfunction "CAPP_9") (pintype "bidirectional"))
    )
    (net (code "19") (name "Net-(ECG-CPLL)") (class "Default")
      (node (ref "C5") (pin "1") (pinfunction "1_1") (pintype "passive"))
      (node (ref "ECG") (pin "11") (pinfunction "CPLL_11") (pintype "bidirectional"))
    )
    (net (code "20") (name "Net-(ECG-EGGN)") (class "Default")
      (node (ref "C39") (pin "2") (pinfunction "2_2") (pintype "passive"))
      (node (ref "C43") (pin "1") (pinfunction "1_1") (pintype "passive"))
      (node (ref "ECG") (pin "7") (pinfunction "EGGN_7") (pintype "bidirectional"))
      (node (ref "R10") (pin "2") (pinfunction "2_2") (pintype "passive"))
    )
    (net (code "21") (name "Net-(ECG-EGGP)") (class "Default")
      (node (ref "C39") (pin "1") (pinfunction "1_1") (pintype "passive"))
      (node (ref "C44") (pin "1") (pinfunction "1_1") (pintype "passive"))
      (node (ref "ECG") (pin "6") (pinfunction "EGGP_6") (pintype "bidirectional"))
      (node (ref "R12") (pin "2") (pinfunction "2_2") (pintype "passive"))
    )
    (net (code "22") (name "Net-(ECG-VBG)") (class "Default")
      (node (ref "C52") (pin "1") (pinfunction "1_1") (pintype "passive"))
      (node (ref "ECG") (pin "27") (pinfunction "VBG_27") (pintype "bidirectional"))
    )
    (net (code "23") (name "Net-(ECG-VCM)") (class "Default")
      (node (ref "C51") (pin "1") (pinfunction "1_1") (pintype "passive"))
      (node (ref "ECG") (pin "25") (pinfunction "VCM_25") (pintype "bidirectional"))
    )
    (net (code "24") (name "Net-(ECG-VREF)") (class "Default")
      (node (ref "C45") (pin "1") (pinfunction "1_1") (pintype "passive"))
      (node (ref "ECG") (pin "23") (pinfunction "VREF_23") (pintype "bidirectional"))
    )
    (net (code "25") (name "Net-(IC1-PROG)") (class "Default")
      (node (ref "IC1") (pin "5") (pinfunction "PROG_5") (pintype "input"))
      (node (ref "Q1") (pin "3") (pinfunction "D_3") (pintype "bidirectional"))
    )
    (net (code "26") (name "Net-(IC1-STAT)") (class "Default")
      (node (ref "IC1") (pin "1") (pinfunction "STAT_1") (pintype "output"))
      (node (ref "R13") (pin "1") (pinfunction "1_1") (pintype "passive"))
    )
    (net (code "27") (name "Net-(IC3-OS)") (class "Default")
      (node (ref "IC3") (pin "3") (pinfunction "OS_3") (pintype "bidirectional"))
      (node (ref "R15") (pin "1") (pinfunction "1_1") (pintype "passive"))
    )
    (net (code "28") (name "Net-(L2-Pad2)") (class "Default")
      (node (ref "L2") (pin "2") (pinfunction "2_2") (pintype "passive"))
      (node (ref "U$5") (pin "P$1") (pinfunction "P$1_P$1") (pintype "bidirectional"))
    )
    (net (code "29") (name "Net-(L3-Pad2)") (class "Default")
      (node (ref "L3") (pin "2") (pinfunction "2_2") (pintype "passive"))
      (node (ref "L4") (pin "1") (pinfunction "1_1") (pintype "passive"))
    )
    (net (code "30") (name "Net-(LED1-A)") (class "Default")
      (node (ref "LED1") (pin "2") (pinfunction "A_2") (pintype "bidirectional"))
      (node (ref "R7") (pin "1") (pinfunction "1_1") (pintype "passive"))
    )
    (net (code "31") (name "Net-(MCU-ANT)") (class "Default")
      (node (ref "C4") (pin "1") (pinfunction "1_1") (pintype "passive"))
      (node (ref "L2") (pin "1") (pinfunction "1_1") (pintype "passive"))
      (node (ref "MCU") (pin "30") (pinfunction "ANT_30") (pintype "bidirectional"))
    )
    (net (code "32") (name "Net-(MCU-DCC)") (class "Default")
      (node (ref "L3") (pin "1") (pinfunction "1_1") (pintype "passive"))
      (node (ref "MCU") (pin "47") (pinfunction "DCC_47") (pintype "output"))
    )
    (net (code "33") (name "Net-(MCU-DEC1)") (class "Default")
      (node (ref "C13") (pin "1") (pinfunction "1_1") (pintype "passive"))
      (node (ref "MCU") (pin "1") (pinfunction "DEC1_1") (pintype "power_in"))
    )
    (net (code "34") (name "Net-(MCU-DEC2)") (class "Default")
      (node (ref "C7") (pin "1") (pinfunction "1_1") (pintype "passive"))
      (node (ref "MCU") (pin "32") (pinfunction "DEC2_32") (pintype "bidirectional"))
    )
    (net (code "35") (name "Net-(MCU-DEC3)") (class "Default")
      (node (ref "C8") (pin "1") (pinfunction "1_1") (pintype "passive"))
      (node (ref "MCU") (pin "33") (pinfunction "DEC3_33") (pintype "bidirectional"))
    )
    (net (code "36") (name "Net-(MCU-DEC4)") (class "Default")
      (node (ref "C11") (pin "1") (pinfunction "1_1") (pintype "passive"))
      (node (ref "L4") (pin "2") (pinfunction "2_2") (pintype "passive"))
      (node (ref "MCU") (pin "46") (pinfunction "DEC4_46") (pintype "power_in"))
    )
    (net (code "37") (name "Net-(MCU-P0.00{slash}XL1)") (class "Default")
      (node (ref "C15") (pin "2") (pinfunction "2_2") (pintype "passive"))
      (node (ref "MCU") (pin "2") (pinfunction "P0.00/XL1_2") (pintype "bidirectional"))
      (node (ref "Y1") (pin "2") (pinfunction "2_2") (pintype "bidirectional"))
    )
    (net (code "38") (name "Net-(MCU-P0.01{slash}XL2)") (class "Default")
      (node (ref "C16") (pin "2") (pinfunction "2_2") (pintype "passive"))
      (node (ref "MCU") (pin "3") (pinfunction "P0.01/XL2_3") (pintype "bidirectional"))
      (node (ref "Y1") (pin "1") (pinfunction "1_1") (pintype "bidirectional"))
    )
    (net (code "39") (name "Net-(MCU-XC1)") (class "Default")
      (node (ref "C3") (pin "1") (pinfunction "1_1") (pintype "passive"))
      (node (ref "MCU") (pin "34") (pinfunction "XC1_34") (pintype "input"))
      (node (ref "Y3") (pin "1") (pinfunction "CRYSTAL_1_1") (pintype "bidirectional"))
    )
    (net (code "40") (name "Net-(MCU-XC2)") (class "Default")
      (node (ref "C2") (pin "1") (pinfunction "1_1") (pintype "passive"))
      (node (ref "MCU") (pin "35") (pinfunction "XC2_35") (pintype "output"))
      (node (ref "Y3") (pin "3") (pinfunction "CRYSTAL_2_3") (pintype "bidirectional"))
    )
    (net (code "41") (name "Net-(Q1-S)") (class "Default")
      (node (ref "Q1") (pin "2") (pinfunction "S_2") (pintype "bidirectional"))
      (node (ref "R2") (pin "1") (pinfunction "1_1") (pintype "passive"))
    )
    (net (code "42") (name "Net-(SWREG-EN)") (class "Default")
      (node (ref "R4") (pin "2") (pinfunction "2_2") (pintype "passive"))
      (node (ref "SWREG") (pin "9") (pinfunction "EN_9") (pintype "bidirectional"))
    )
    (net (code "43") (name "RESET") (class "Default")
      (node (ref "MCU") (pin "24") (pinfunction "P0.21/RESET_24") (pintype "bidirectional"))
      (node (ref "RESET") (pin "1") (pinfunction "1_1") (pintype "passive"))
    )
    (net (code "44") (name "RXD") (class "Default")
      (node (ref "MCU") (pin "9") (pinfunction "P0.07_9") (pintype "bidirectional"))
      (node (ref "RXD") (pin "1") (pinfunction "1_1") (pintype "passive"))
    )
    (net (code "45") (name "SCL") (class "Default")
      (node (ref "IC3") (pin "2") (pinfunction "SCL_2") (pintype "bidirectional"))
      (node (ref "MCU") (pin "38") (pinfunction "P0.26_38") (pintype "bidirectional"))
    )
    (net (code "46") (name "SCLK") (class "Default")
      (node (ref "ECG") (pin "16") (pinfunction "SCLK_16") (pintype "bidirectional"))
      (node (ref "IC4") (pin "6") (pinfunction "SCK_6") (pintype "bidirectional"))
      (node (ref "MCU") (pin "11") (pinfunction "P0.09/NFC1_11") (pintype "bidirectional"))
    )
    (net (code "47") (name "SDA") (class "Default")
      (node (ref "IC3") (pin "1") (pinfunction "SDA_1") (pintype "bidirectional"))
      (node (ref "MCU") (pin "37") (pinfunction "P0.25_37") (pintype "bidirectional"))
    )
    (net (code "48") (name "SF_CS") (class "Default")
      (node (ref "IC4") (pin "1") (pinfunction "~{CS}_1") (pintype "bidirectional"))
      (node (ref "MCU") (pin "18") (pinfunction "P0.15_18") (pintype "bidirectional"))
    )
    (net (code "49") (name "SWCLK") (class "Default")
      (node (ref "MCU") (pin "25") (pinfunction "SWDCLK_25") (pintype "input"))
      (node (ref "SWCLK") (pin "1") (pinfunction "1_1") (pintype "passive"))
    )
    (net (code "50") (name "SWDIO") (class "Default")
      (node (ref "MCU") (pin "26") (pinfunction "SWDIO_26") (pintype "bidirectional"))
      (node (ref "SWDIO") (pin "1") (pinfunction "1_1") (pintype "passive"))
    )
    (net (code "51") (name "SWITCHA") (class "Default")
      (node (ref "MCU") (pin "23") (pinfunction "P0.20_23") (pintype "bidirectional"))
      (node (ref "R14") (pin "1") (pinfunction "1_1") (pintype "passive"))
      (node (ref "S2") (pin "3") (pinfunction "3_3") (pintype "bidirectional"))
    )
    (net (code "52") (name "TXD") (class "Default")
      (node (ref "MCU") (pin "8") (pinfunction "P0.06_8") (pintype "bidirectional"))
      (node (ref "TXD") (pin "1") (pinfunction "1_1") (pintype "passive"))
    )
    (net (code "53") (name "VBUS") (class "Default")
      (node (ref "C23") (pin "1") (pinfunction "1_1") (pintype "passive"))
      (node (ref "D2") (pin "A") (pinfunction "A_A") (pintype "passive"))
      (node (ref "IC1") (pin "4") (pinfunction "VDD_4") (pintype "power_in"))
      (node (ref "J1") (pin "1") (pinfunction "1_1") (pintype "bidirectional"))
      (node (ref "Q3") (pin "1") (pinfunction "G_1") (pintype "passive"))
      (node (ref "R3") (pin "2") (pinfunction "2_2") (pintype "passive"))
    )
    (net (code "54") (name "VINBAT") (class "Default")
      (node (ref "C24") (pin "1") (pinfunction "1_1") (pintype "passive"))
      (node (ref "D2") (pin "C") (pinfunction "C_C") (pintype "passive"))
      (node (ref "IC2") (pin "2") (pinfunction "V_IN_2") (pintype "bidirectional"))
      (node (ref "Q3") (pin "2") (pinfunction "S_2") (pintype "passive"))
      (node (ref "R4") (pin "1") (pinfunction "1_1") (pintype "passive"))
      (node (ref "SWREG") (pin "5") (pinfunction "VIN_5") (pintype "bidirectional"))
      (node (ref "SWREG") (pin "6") (pinfunction "VIN_6") (pintype "bidirectional"))
    )
    (net (code "55") (name "V_BATT") (class "Default")
      (node (ref "BATTERY") (pin "1") (pinfunction "1_1") (pintype "passive"))
      (node (ref "C19") (pin "1") (pinfunction "1_1") (pintype "passive"))
      (node (ref "IC1") (pin "3") (pinfunction "VBAT_3") (pintype "bidirectional"))
      (node (ref "Q3") (pin "3") (pinfunction "D_3") (pintype "passive"))
      (node (ref "R6") (pin "2") (pinfunction "2_2") (pintype "passive"))
    )
    (net (code "56") (name "unconnected-(ECG-INT2B-Pad20)") (class "Default")
      (node (ref "ECG") (pin "20") (pinfunction "INT2B_20") (pintype "bidirectional"))
    )
    (net (code "57") (name "unconnected-(ECG-INTB-Pad21)") (class "Default")
      (node (ref "ECG") (pin "21") (pinfunction "INTB_21") (pintype "bidirectional"))
    )
    (net (code "58") (name "unconnected-(IC3-EP-Pad9)") (class "Default")
      (node (ref "IC3") (pin "9") (pinfunction "EP_9") (pintype "bidirectional"))
    )
    (net (code "59") (name "unconnected-(IC4-~{HOLD_(I}{slash}O3)-Pad7)") (class "Default")
      (node (ref "IC4") (pin "7") (pinfunction "~{HOLD_(I}/O3)_7") (pintype "bidirectional"))
    )
    (net (code "60") (name "unconnected-(IC4-~{WP_(I}{slash}O2)-Pad3)") (class "Default")
      (node (ref "IC4") (pin "3") (pinfunction "~{WP_(I}/O2)_3") (pintype "bidirectional"))
    )
    (net (code "61") (name "unconnected-(J1-Pad2)") (class "Default")
      (node (ref "J1") (pin "2") (pinfunction "2_2") (pintype "bidirectional"))
    )
    (net (code "62") (name "unconnected-(J1-Pad3)") (class "Default")
      (node (ref "J1") (pin "3") (pinfunction "3_3") (pintype "bidirectional"))
    )
    (net (code "63") (name "unconnected-(J1-Pad4)") (class "Default")
      (node (ref "J1") (pin "4") (pinfunction "4_4") (pintype "bidirectional"))
    )
    (net (code "64") (name "unconnected-(J1-Pad6)") (class "Default")
      (node (ref "J1") (pin "6") (pinfunction "6_6") (pintype "bidirectional"))
    )
    (net (code "65") (name "unconnected-(J1-Pad7)") (class "Default")
      (node (ref "J1") (pin "7") (pinfunction "7_7") (pintype "bidirectional"))
    )
    (net (code "66") (name "unconnected-(J1-Pad8)") (class "Default")
      (node (ref "J1") (pin "8") (pinfunction "8_8") (pintype "bidirectional"))
    )
    (net (code "67") (name "unconnected-(J1-Pad9)") (class "Default")
      (node (ref "J1") (pin "9") (pinfunction "9_9") (pintype "bidirectional"))
    )
    (net (code "68") (name "unconnected-(J1-Pad10)") (class "Default")
      (node (ref "J1") (pin "10") (pinfunction "10_10") (pintype "bidirectional"))
    )
    (net (code "69") (name "unconnected-(J1-Pad11)") (class "Default")
      (node (ref "J1") (pin "11") (pinfunction "11_11") (pintype "bidirectional"))
    )
    (net (code "70") (name "unconnected-(MCU-N.C.-Pad44)") (class "Default")
      (node (ref "MCU") (pin "44") (pinfunction "N.C._44") (pintype "no_connect"))
    )
    (net (code "71") (name "unconnected-(MCU-P0.03{slash}AIN1-Pad5)") (class "Default")
      (node (ref "MCU") (pin "5") (pinfunction "P0.03/AIN1_5") (pintype "bidirectional"))
    )
    (net (code "72") (name "unconnected-(MCU-P0.04{slash}AIN2-Pad6)") (class "Default")
      (node (ref "MCU") (pin "6") (pinfunction "P0.04/AIN2_6") (pintype "bidirectional"))
    )
    (net (code "73") (name "unconnected-(MCU-P0.05{slash}AIN3-Pad7)") (class "Default")
      (node (ref "MCU") (pin "7") (pinfunction "P0.05/AIN3_7") (pintype "bidirectional"))
    )
    (net (code "74") (name "unconnected-(MCU-P0.16-Pad19)") (class "Default")
      (node (ref "MCU") (pin "19") (pinfunction "P0.16_19") (pintype "bidirectional"))
    )
    (net (code "75") (name "unconnected-(MCU-P0.17-Pad20)") (class "Default")
      (node (ref "MCU") (pin "20") (pinfunction "P0.17_20") (pintype "bidirectional"))
    )
    (net (code "76") (name "unconnected-(MCU-P0.18{slash}SWO-Pad21)") (class "Default")
      (node (ref "MCU") (pin "21") (pinfunction "P0.18/SWO_21") (pintype "bidirectional"))
    )
    (net (code "77") (name "unconnected-(MCU-P0.19-Pad22)") (class "Default")
      (node (ref "MCU") (pin "22") (pinfunction "P0.19_22") (pintype "bidirectional"))
    )
    (net (code "78") (name "unconnected-(MCU-P0.22-Pad27)") (class "Default")
      (node (ref "MCU") (pin "27") (pinfunction "P0.22_27") (pintype "bidirectional"))
    )
    (net (code "79") (name "unconnected-(MCU-P0.23-Pad28)") (class "Default")
      (node (ref "MCU") (pin "28") (pinfunction "P0.23_28") (pintype "bidirectional"))
    )
    (net (code "80") (name "unconnected-(MCU-P0.24-Pad29)") (class "Default")
      (node (ref "MCU") (pin "29") (pinfunction "P0.24_29") (pintype "bidirectional"))
    )
    (net (code "81") (name "unconnected-(MCU-P0.28-Pad40)") (class "Default")
      (node (ref "MCU") (pin "40") (pinfunction "P0.28_40") (pintype "bidirectional"))
    )
    (net (code "82") (name "unconnected-(MCU-P0.29-Pad41)") (class "Default")
      (node (ref "MCU") (pin "41") (pinfunction "P0.29_41") (pintype "bidirectional"))
    )
    (net (code "83") (name "unconnected-(MCU-P0.30-Pad42)") (class "Default")
      (node (ref "MCU") (pin "42") (pinfunction "P0.30_42") (pintype "bidirectional"))
    )
    (net (code "84") (name "unconnected-(MCU-P0.31-Pad43)") (class "Default")
      (node (ref "MCU") (pin "43") (pinfunction "P0.31_43") (pintype "bidirectional"))
    )
    (net (code "85") (name "unconnected-(S2-Pad2)") (class "Default")
      (node (ref "S2") (pin "2") (pinfunction "2_2") (pintype "bidirectional"))
    )
    (net (code "86") (name "unconnected-(S2-Pad4)") (class "Default")
      (node (ref "S2") (pin "4") (pinfunction "4_4") (pintype "bidirectional"))
    )
  )
)
